# us__2shc.net
KiCad netlist of a schematic drawn in Altium Designer
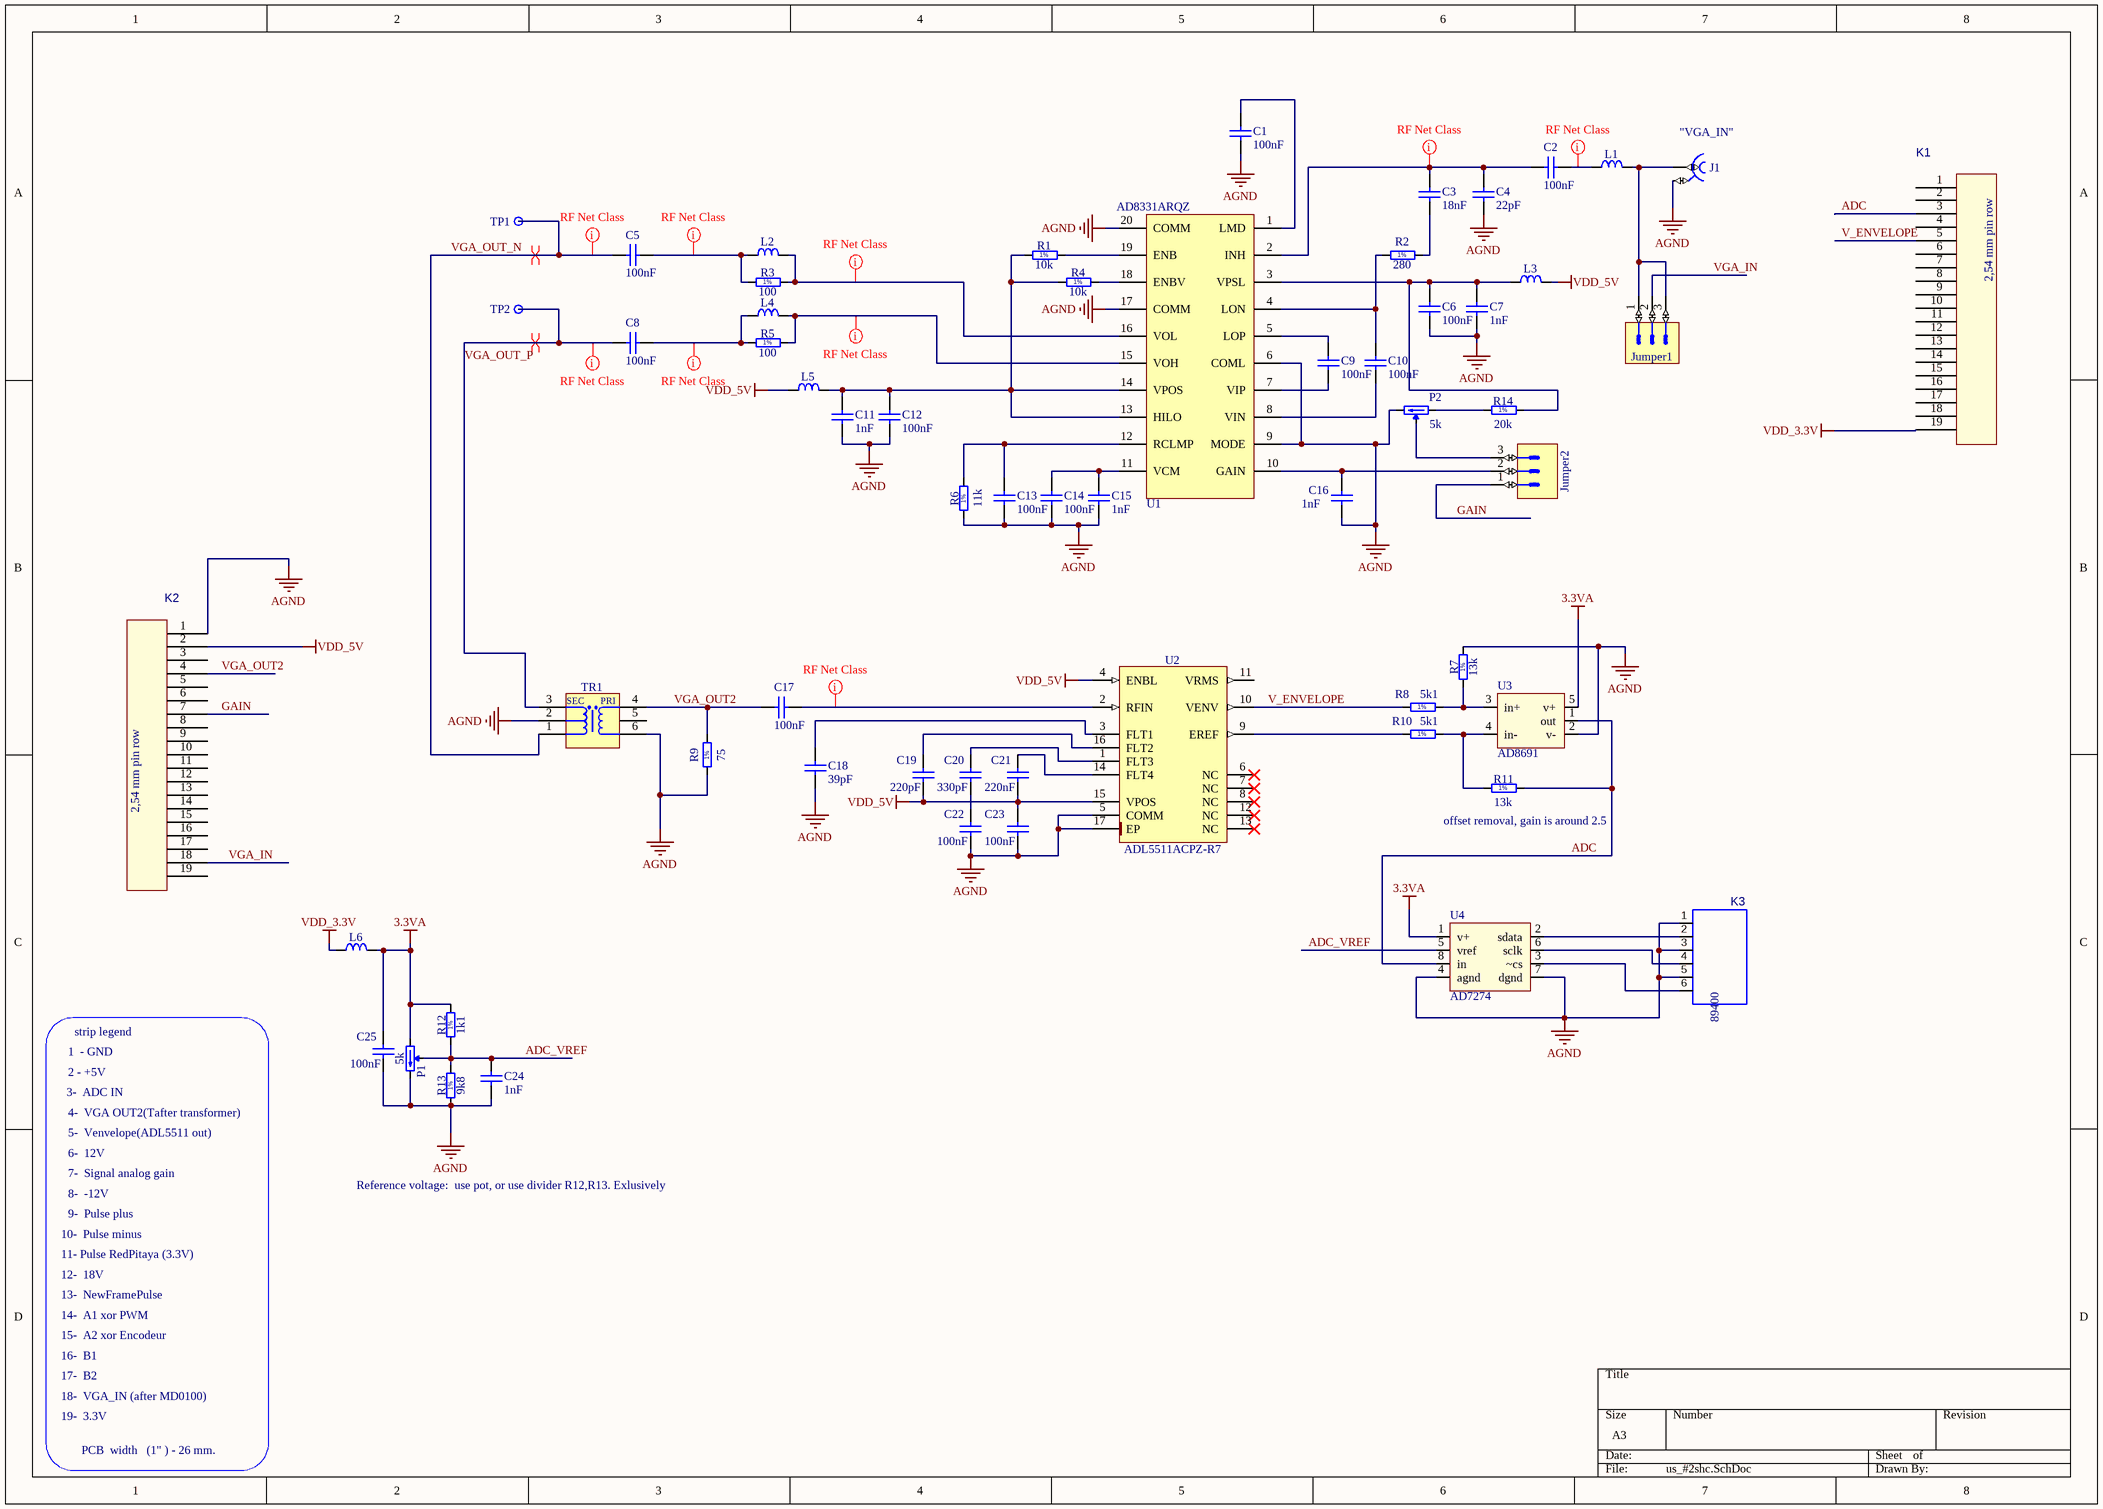
[diagram p0: us_#2shc.SchDoc]

(export (version "E")
  (design (tool "Eeschema 10.0.6"))
  (components
    (comp (ref "C1")
      (value "100nF")
      (footprint "SM0603 _3D_cap")
      (description "Capacitor  0603 inch")
      (fields (field (name "Comment") "cap0603") (field (name "PUBLISHER") "Altium Limited"))
      (libsource (lib "alt_vovan") (part "cap0603"))
    )
    (comp (ref "C2")
      (value "100nF")
      (footprint "SM0603 _3D_cap")
      (description "Capacitor  0603 inch")
      (fields (field (name "Comment") "cap0603") (field (name "PUBLISHER") "Altium Limited"))
      (libsource (lib "alt_vovan") (part "cap0603"))
    )
    (comp (ref "C3")
      (value "18nF")
      (footprint "SM0603 _3D_cap")
      (description "Capacitor  0603 inch")
      (fields (field (name "Comment") "cap0603") (field (name "PUBLISHER") "Altium Limited"))
      (libsource (lib "alt_vovan") (part "cap0603"))
    )
    (comp (ref "C4")
      (value "22pF")
      (footprint "SM0603 _3D_cap")
      (description "Capacitor  0603 inch")
      (fields (field (name "Comment") "cap0603") (field (name "PUBLISHER") "Altium Limited"))
      (libsource (lib "alt_vovan") (part "cap0603"))
    )
    (comp (ref "C5")
      (value "100nF")
      (footprint "SM0603 _3D_cap")
      (description "Capacitor  0603 inch")
      (fields (field (name "Comment") "cap0603") (field (name "PUBLISHER") "Altium Limited"))
      (libsource (lib "alt_vovan") (part "cap0603"))
    )
    (comp (ref "C6")
      (value "100nF")
      (footprint "SM0603 _3D_cap")
      (description "Capacitor  0603 inch")
      (fields (field (name "Comment") "cap0603") (field (name "PUBLISHER") "Altium Limited"))
      (libsource (lib "alt_vovan") (part "cap0603"))
    )
    (comp (ref "C7")
      (value "1nF")
      (footprint "SM0603 _3D_cap")
      (description "Capacitor  0603 inch")
      (fields (field (name "Comment") "cap0603") (field (name "PUBLISHER") "Altium Limited"))
      (libsource (lib "alt_vovan") (part "cap0603"))
    )
    (comp (ref "C8")
      (value "100nF")
      (footprint "SM0603 _3D_cap")
      (description "Capacitor  0603 inch")
      (fields (field (name "Comment") "cap0603") (field (name "PUBLISHER") "Altium Limited"))
      (libsource (lib "alt_vovan") (part "cap0603"))
    )
    (comp (ref "C9")
      (value "100nF")
      (footprint "SM0603 _3D_cap")
      (description "Capacitor  0603 inch")
      (fields (field (name "Comment") "cap0603") (field (name "PUBLISHER") "Altium Limited"))
      (libsource (lib "alt_vovan") (part "cap0603"))
    )
    (comp (ref "C10")
      (value "100nF")
      (footprint "SM0603 _3D_cap")
      (description "Capacitor  0603 inch")
      (fields (field (name "Comment") "cap0603") (field (name "PUBLISHER") "Altium Limited"))
      (libsource (lib "alt_vovan") (part "cap0603"))
    )
    (comp (ref "C11")
      (value "1nF")
      (footprint "SM0603 _3D_cap")
      (description "Capacitor  0603 inch")
      (fields (field (name "Comment") "cap0603") (field (name "PUBLISHER") "Altium Limited"))
      (libsource (lib "alt_vovan") (part "cap0603"))
    )
    (comp (ref "C12")
      (value "100nF")
      (footprint "SM0603 _3D_cap")
      (description "Capacitor  0603 inch")
      (fields (field (name "Comment") "cap0603") (field (name "PUBLISHER") "Altium Limited"))
      (libsource (lib "alt_vovan") (part "cap0603"))
    )
    (comp (ref "C13")
      (value "100nF")
      (footprint "SM0603 _3D_cap")
      (description "Capacitor  0603 inch")
      (fields (field (name "Comment") "cap0603") (field (name "PUBLISHER") "Altium Limited"))
      (libsource (lib "alt_vovan") (part "cap0603"))
    )
    (comp (ref "C14")
      (value "100nF")
      (footprint "SM0603 _3D_cap")
      (description "Capacitor  0603 inch")
      (fields (field (name "Comment") "cap0603") (field (name "PUBLISHER") "Altium Limited"))
      (libsource (lib "alt_vovan") (part "cap0603"))
    )
    (comp (ref "C15")
      (value "1nF")
      (footprint "SM0603 _3D_cap")
      (description "Capacitor  0603 inch")
      (fields (field (name "Comment") "cap0603") (field (name "PUBLISHER") "Altium Limited"))
      (libsource (lib "alt_vovan") (part "cap0603"))
    )
    (comp (ref "C16")
      (value "1nF")
      (footprint "SM0603 _3D_cap")
      (description "Capacitor  0603 inch")
      (fields (field (name "Comment") "cap0603") (field (name "PUBLISHER") "Altium Limited"))
      (libsource (lib "alt_vovan") (part "cap0603"))
    )
    (comp (ref "C17")
      (value "100nF")
      (footprint "SM0603 _3D_cap")
      (description "Capacitor  0603 inch")
      (fields (field (name "Comment") "cap0603") (field (name "PUBLISHER") "Altium Limited"))
      (libsource (lib "alt_vovan") (part "cap0603"))
    )
    (comp (ref "C18")
      (value "39pF")
      (footprint "SM0603 _3D_cap")
      (description "Capacitor  0603 inch")
      (fields (field (name "Comment") "cap0603") (field (name "PUBLISHER") "Altium Limited"))
      (libsource (lib "alt_vovan") (part "cap0603"))
    )
    (comp (ref "C19")
      (value "220pF")
      (footprint "SM0603 _3D_cap")
      (description "Capacitor  0603 inch")
      (fields (field (name "Comment") "cap0603") (field (name "PUBLISHER") "Altium Limited"))
      (libsource (lib "alt_vovan") (part "cap0603"))
    )
    (comp (ref "C20")
      (value "330pF")
      (footprint "SM0603 _3D_cap")
      (description "Capacitor  0603 inch")
      (fields (field (name "Comment") "cap0603") (field (name "PUBLISHER") "Altium Limited"))
      (libsource (lib "alt_vovan") (part "cap0603"))
    )
    (comp (ref "C21")
      (value "220nF")
      (footprint "SM0603 _3D_cap")
      (description "Capacitor  0603 inch")
      (fields (field (name "Comment") "cap0603") (field (name "PUBLISHER") "Altium Limited"))
      (libsource (lib "alt_vovan") (part "cap0603"))
    )
    (comp (ref "C22")
      (value "100nF")
      (footprint "SM0603 _3D_cap")
      (description "Capacitor  0603 inch")
      (fields (field (name "Comment") "cap0603") (field (name "PUBLISHER") "Altium Limited"))
      (libsource (lib "alt_vovan") (part "cap0603"))
    )
    (comp (ref "C23")
      (value "100nF")
      (footprint "SM0603 _3D_cap")
      (description "Capacitor  0603 inch")
      (fields (field (name "Comment") "cap0603") (field (name "PUBLISHER") "Altium Limited"))
      (libsource (lib "alt_vovan") (part "cap0603"))
    )
    (comp (ref "C24")
      (value "1nF")
      (footprint "SM0603 _3D_cap")
      (description "Capacitor  0603 inch")
      (fields (field (name "Comment") "cap0603") (field (name "PUBLISHER") "Altium Limited"))
      (libsource (lib "alt_vovan") (part "cap0603"))
    )
    (comp (ref "C25")
      (value "100nF")
      (footprint "SM0603 _3D_cap")
      (description "Capacitor  0603 inch")
      (fields (field (name "Comment") "cap0603") (field (name "PUBLISHER") "Altium Limited"))
      (libsource (lib "alt_vovan") (part "cap0603"))
    )
    (comp (ref "J1")
      (value "SMA")
      (footprint "AMPHENOL_132357-11")
      (fields
        (field (name "PART NUMBER") "AMPHENOL_132357-11")
        (field (name "MANUFACTURER") "AMPHENOL")
        (field (name "MANUFACTURER PART NUMBER") "132357-11")
        (field (name "AUTHOR") "CERN DEM JLC")
      )
      (libsource (lib "echOpen_ADC_Card") (part "Coax_1Female_1Shield"))
    )
    (comp (ref "Jumper1")
      (value "~")
      (footprint "SULLINS_GRPB031VWVN")
      (description "Connector 3 Male")
      (fields
        (field (name "PART NUMBER") "SULLINS_GRPB031VWVN")
        (field (name "MANUFACTURER") "SULLINS")
        (field (name "AUTHOR") "S. Jafar")
      )
      (libsource (lib "") (part "Connector 3 Male_1"))
    )
    (comp (ref "Jumper2")
      (value "~")
      (footprint "SULLINS_GRPB031VWVN")
      (description "Connector 3 Male")
      (fields
        (field (name "PART NUMBER") "SULLINS_GRPB031VWVN")
        (field (name "MANUFACTURER") "SULLINS")
        (field (name "AUTHOR") "S. Jafar")
      )
      (libsource (lib "Sof-Connectors") (part "Connector 3 Male"))
    )
    (comp (ref "K1")
      (value "PLS_2.54mm-19")
      (footprint "PLS_2.54mm-19")
      (libsource (lib "") (part "PLS_2.54mm-19_1"))
    )
    (comp (ref "K2")
      (value "PLS_2.54mm-19")
      (footprint "PLS_2.54mm-19")
      (libsource (lib "alt_vovan") (part "PLS_2.54mm-19"))
    )
    (comp (ref "K3")
      (value "Molex_89400_061")
      (footprint "Molex_89400-061")
      (description "6 pin vertical 2mm")
      (libsource (lib "alt_vovan") (part "Molex_89400_061"))
    )
    (comp (ref "L1")
      (value "75R@100MHz")
      (footprint "SM_0805_INDUCTANCE _3D")
      (description "chip inductance")
      (fields
        (field (name "PART NUMBER") "IND0805_MURATA_BLM21BB750SN1D")
        (field (name "POWER") "700mA")
        (field (name "AUTHOR") "S. Jafar")
      )
      (libsource (lib "alt_vovan") (part "Ind_Chip"))
    )
    (comp (ref "L2")
      (value "75R@100MHz")
      (footprint "SM_0805_INDUCTANCE _3D")
      (description "chip inductance")
      (fields
        (field (name "PART NUMBER") "IND0805_MURATA_BLM21BB750SN1D")
        (field (name "POWER") "700mA")
        (field (name "AUTHOR") "S. Jafar")
      )
      (libsource (lib "alt_vovan") (part "Ind_Chip"))
    )
    (comp (ref "L3")
      (value "75R@100MHz")
      (footprint "SM_0805_INDUCTANCE _3D")
      (description "chip inductance")
      (fields
        (field (name "PART NUMBER") "IND0805_MURATA_BLM21BB750SN1D")
        (field (name "POWER") "700mA")
        (field (name "AUTHOR") "S. Jafar")
      )
      (libsource (lib "alt_vovan") (part "Ind_Chip"))
    )
    (comp (ref "L4")
      (value "75R@100MHz")
      (footprint "SM_0805_INDUCTANCE _3D")
      (description "chip inductance")
      (fields
        (field (name "PART NUMBER") "IND0805_MURATA_BLM21BB750SN1D")
        (field (name "POWER") "700mA")
        (field (name "AUTHOR") "S. Jafar")
      )
      (libsource (lib "alt_vovan") (part "Ind_Chip"))
    )
    (comp (ref "L5")
      (value "75R@100MHz")
      (footprint "SM_0805_INDUCTANCE _3D")
      (description "chip inductance")
      (fields
        (field (name "PART NUMBER") "IND0805_MURATA_BLM21BB750SN1D")
        (field (name "POWER") "700mA")
        (field (name "AUTHOR") "S. Jafar")
      )
      (libsource (lib "alt_vovan") (part "Ind_Chip"))
    )
    (comp (ref "L6")
      (value "75R@100MHz")
      (footprint "SM_0805_INDUCTANCE _3D")
      (description "chip inductance")
      (fields
        (field (name "PART NUMBER") "IND0805_MURATA_BLM21BB750SN1D")
        (field (name "POWER") "700mA")
        (field (name "AUTHOR") "S. Jafar")
      )
      (libsource (lib "alt_vovan") (part "Ind_Chip"))
    )
    (comp (ref "P1")
      (value "5k")
      (footprint "TRIM_BOURNS_3223W")
      (description "Trimming Potentiometer")
      (fields
        (field (name "PART NUMBER") "TRIM_11T_5K_BOURNS_3223W-1-502E")
        (field (name "POWER") "0.125W")
        (field (name "AUTHOR") "CERN DEM JLC")
      )
      (libsource (lib "echOpen_ADC_Card") (part "Trimming Potentiometer"))
    )
    (comp (ref "P2")
      (value "5k")
      (footprint "TRIM_BOURNS_3223W")
      (description "Trimming Potentiometer")
      (fields
        (field (name "PART NUMBER") "TRIM_11T_5K_BOURNS_3223W-1-502E")
        (field (name "POWER") "0.125W")
        (field (name "AUTHOR") "CERN DEM JLC")
      )
      (libsource (lib "echOpen_ADC_Card") (part "Trimming Potentiometer"))
    )
    (comp (ref "R1")
      (value "10k")
      (footprint "SM0603_3D_res")
      (description "Res_0603_1%_EU")
      (fields
        (field (name "PART NUMBER") "R1206_4K7_1%_0.25W_100PPM")
        (field (name "POWER") "0.25W")
        (field (name "AUTHOR") "CERN DEM JLC")
      )
      (libsource (lib "alt_vovan") (part "Res_0603_1%_EU"))
    )
    (comp (ref "R2")
      (value "280")
      (footprint "SM0603_3D_res")
      (description "Res_0603_1%_EU")
      (fields
        (field (name "PART NUMBER") "R1206_4K7_1%_0.25W_100PPM")
        (field (name "POWER") "0.25W")
        (field (name "AUTHOR") "CERN DEM JLC")
      )
      (libsource (lib "alt_vovan") (part "Res_0603_1%_EU"))
    )
    (comp (ref "R3")
      (value "100")
      (footprint "SM0603_3D_res")
      (description "Res_0603_1%_EU")
      (fields
        (field (name "PART NUMBER") "R1206_4K7_1%_0.25W_100PPM")
        (field (name "POWER") "0.25W")
        (field (name "AUTHOR") "CERN DEM JLC")
      )
      (libsource (lib "alt_vovan") (part "Res_0603_1%_EU"))
    )
    (comp (ref "R4")
      (value "10k")
      (footprint "SM0603_3D_res")
      (description "Res_0603_1%_EU")
      (fields
        (field (name "PART NUMBER") "R1206_4K7_1%_0.25W_100PPM")
        (field (name "POWER") "0.25W")
        (field (name "AUTHOR") "CERN DEM JLC")
      )
      (libsource (lib "alt_vovan") (part "Res_0603_1%_EU"))
    )
    (comp (ref "R5")
      (value "100")
      (footprint "SM0603_3D_res")
      (description "Res_0603_1%_EU")
      (fields
        (field (name "PART NUMBER") "R1206_4K7_1%_0.25W_100PPM")
        (field (name "POWER") "0.25W")
        (field (name "AUTHOR") "CERN DEM JLC")
      )
      (libsource (lib "alt_vovan") (part "Res_0603_1%_EU"))
    )
    (comp (ref "R6")
      (value "11k")
      (footprint "SM0603_3D_res")
      (description "Res_0603_1%_EU")
      (fields
        (field (name "PART NUMBER") "R1206_4K7_1%_0.25W_100PPM")
        (field (name "POWER") "0.25W")
        (field (name "AUTHOR") "CERN DEM JLC")
      )
      (libsource (lib "alt_vovan") (part "Res_0603_1%_EU"))
    )
    (comp (ref "R7")
      (value "13k")
      (footprint "SM0603_3D_res")
      (description "Res_0603_1%_EU")
      (fields
        (field (name "PART NUMBER") "R1206_4K7_1%_0.25W_100PPM")
        (field (name "POWER") "0.25W")
        (field (name "AUTHOR") "CERN DEM JLC")
      )
      (libsource (lib "alt_vovan") (part "Res_0603_1%_EU"))
    )
    (comp (ref "R8")
      (value "5k1")
      (footprint "SM0603_3D_res")
      (description "Res_0603_1%_EU")
      (fields
        (field (name "PART NUMBER") "R1206_4K7_1%_0.25W_100PPM")
        (field (name "POWER") "0.25W")
        (field (name "AUTHOR") "CERN DEM JLC")
      )
      (libsource (lib "alt_vovan") (part "Res_0603_1%_EU"))
    )
    (comp (ref "R9")
      (value "75")
      (footprint "SM0603_3D_res")
      (description "Res_0603_1%_EU")
      (fields
        (field (name "PART NUMBER") "R1206_4K7_1%_0.25W_100PPM")
        (field (name "POWER") "0.25W")
        (field (name "AUTHOR") "CERN DEM JLC")
      )
      (libsource (lib "alt_vovan") (part "Res_0603_1%_EU"))
    )
    (comp (ref "R10")
      (value "5k1")
      (footprint "SM0603_3D_res")
      (description "Res_0603_1%_EU")
      (fields
        (field (name "PART NUMBER") "R1206_4K7_1%_0.25W_100PPM")
        (field (name "POWER") "0.25W")
        (field (name "AUTHOR") "CERN DEM JLC")
      )
      (libsource (lib "alt_vovan") (part "Res_0603_1%_EU"))
    )
    (comp (ref "R11")
      (value "13k")
      (footprint "SM0603_3D_res")
      (description "Res_0603_1%_EU")
      (fields
        (field (name "PART NUMBER") "R1206_4K7_1%_0.25W_100PPM")
        (field (name "POWER") "0.25W")
        (field (name "AUTHOR") "CERN DEM JLC")
      )
      (libsource (lib "alt_vovan") (part "Res_0603_1%_EU"))
    )
    (comp (ref "R12")
      (value "1k1")
      (footprint "SM0603_3D_res")
      (description "Res_0603_1%_EU")
      (fields
        (field (name "PART NUMBER") "R1206_4K7_1%_0.25W_100PPM")
        (field (name "POWER") "0.25W")
        (field (name "AUTHOR") "CERN DEM JLC")
      )
      (libsource (lib "alt_vovan") (part "Res_0603_1%_EU"))
    )
    (comp (ref "R13")
      (value "9k8")
      (footprint "SM0603_3D_res")
      (description "Res_0603_1%_EU")
      (fields
        (field (name "PART NUMBER") "R1206_4K7_1%_0.25W_100PPM")
        (field (name "POWER") "0.25W")
        (field (name "AUTHOR") "CERN DEM JLC")
      )
      (libsource (lib "alt_vovan") (part "Res_0603_1%_EU"))
    )
    (comp (ref "R14")
      (value "20k")
      (footprint "SM0603_3D_res")
      (description "Res_0603_1%_EU")
      (fields
        (field (name "PART NUMBER") "R1206_4K7_1%_0.25W_100PPM")
        (field (name "POWER") "0.25W")
        (field (name "AUTHOR") "CERN DEM JLC")
      )
      (libsource (lib "alt_vovan") (part "Res_0603_1%_EU"))
    )
    (comp (ref "TP1")
      (value "Test Point")
      (footprint "NICOMATIC_C12000B")
      (fields
        (field (name "PART NUMBER") "NICOMATIC_C12000B")
        (field (name "MANUFACTURER") "NICOMATIC")
        (field (name "MANUFACTURER PART NUMBER") "C12000B")
        (field (name "AUTHOR") "CERN DEM JLC")
      )
      (libsource (lib "Sof-Connectors") (part "Test Point"))
    )
    (comp (ref "TP2")
      (value "Test Point")
      (footprint "NICOMATIC_C12000B")
      (fields
        (field (name "PART NUMBER") "NICOMATIC_C12000B")
        (field (name "MANUFACTURER") "NICOMATIC")
        (field (name "MANUFACTURER PART NUMBER") "C12000B")
        (field (name "AUTHOR") "CERN DEM JLC")
      )
      (libsource (lib "Sof-Connectors") (part "Test Point"))
    )
    (comp (ref "TR1")
      (value "1:1")
      (footprint "XFMR_MINI-CIRCUITS_KK81")
      (description "50 Ohm 0.015 To 300MHz RF Transformers")
      (fields
        (field (name "PART NUMBER") "XFMR_MINI-CIRCUITS_T1-6T-KK81")
        (field (name "MANUFACTURER") "MINI-CIRCUITS")
        (field (name "AUTHOR") "S. Jafar")
      )
      (libsource (lib "Sof-Inductors & Transformers") (part "XFMR_MINI-CIRCUITS_T1-6T-KK81"))
    )
    (comp (ref "U1")
      (value "AD8331ARQZ")
      (footprint "SOP64P600X175-20N")
      (fields (field (name "MANUFACTURER") "Analog Devices") (field (name "AUTHOR") "S. Jafar"))
      (libsource (lib "Sof-ICs And Semiconductors") (part "AD8331"))
    )
    (comp (ref "U2")
      (value "ADL5511ACPZ-R7")
      (footprint "QFN50P300X300X80-17N-S175")
      (description "DC to 6 GHz Envelope and TruPwr RMS Detector")
      (fields (field (name "MANUFACTURER") "ANALOG DEVICES") (field (name "AUTHOR") "CERN DEM JLC"))
      (libsource (lib "Sof-ICs And Semiconductors") (part "ADL5511"))
    )
    (comp (ref "U3")
      (value "AD8691")
      (footprint "TSOT-5(RT-5)")
      (libsource (lib "alt_vovan") (part "OpAmp_TSOT5"))
    )
    (comp (ref "U4")
      (value "AD7274")
      (footprint "RM-8")
      (description "adc serial")
      (libsource (lib "alt_vovan") (part "AD7274"))
    )
  )
  (nets
    (net (code "1") (name "/ADC") (class "Default")
      (node (ref "K1") (pin "3") (pinfunction "3_3") (pintype "passive"))
      (node (ref "R11") (pin "2") (pinfunction "2_2") (pintype "passive"))
      (node (ref "U3") (pin "1") (pinfunction "out_1") (pintype "passive"))
      (node (ref "U4") (pin "8") (pinfunction "in_8") (pintype "passive"))
    )
    (net (code "2") (name "/ADC_VREF") (class "Default")
      (node (ref "C24") (pin "2") (pinfunction "2_2") (pintype "passive"))
      (node (ref "P1") (pin "2") (pinfunction "W_2") (pintype "passive"))
      (node (ref "R12") (pin "1") (pinfunction "1_1") (pintype "passive"))
      (node (ref "R13") (pin "2") (pinfunction "2_2") (pintype "passive"))
      (node (ref "U4") (pin "5") (pinfunction "vref_5") (pintype "passive"))
    )
    (net (code "3") (name "/GAIN") (class "Default")
      (node (ref "Jumper2") (pin "1") (pinfunction "1_1") (pintype "bidirectional"))
      (node (ref "K2") (pin "7") (pinfunction "7_7") (pintype "passive"))
    )
    (net (code "4") (name "/VGA_IN") (class "Default")
      (node (ref "Jumper1") (pin "2") (pinfunction "2_2") (pintype "bidirectional"))
      (node (ref "K2") (pin "18") (pinfunction "18_18") (pintype "passive"))
    )
    (net (code "5") (name "/VGA_OUT2") (class "Default")
      (node (ref "C17") (pin "1") (pinfunction "1_1") (pintype "passive"))
      (node (ref "K2") (pin "4") (pinfunction "4_4") (pintype "passive"))
      (node (ref "R9") (pin "2") (pinfunction "2_2") (pintype "passive"))
      (node (ref "TR1") (pin "4") (pinfunction "SDOT_4") (pintype "passive"))
    )
    (net (code "6") (name "/VGA_OUT_N") (class "Default")
      (node (ref "C5") (pin "1") (pinfunction "1_1") (pintype "passive"))
      (node (ref "TP1") (pin "1") (pinfunction "1_1") (pintype "bidirectional"))
      (node (ref "TR1") (pin "1") (pinfunction "P_1") (pintype "passive"))
    )
    (net (code "7") (name "/VGA_OUT_P") (class "Default")
      (node (ref "C8") (pin "2") (pinfunction "2_2") (pintype "passive"))
      (node (ref "TP2") (pin "1") (pinfunction "1_1") (pintype "bidirectional"))
      (node (ref "TR1") (pin "3") (pinfunction "PDOT_3") (pintype "passive"))
    )
    (net (code "8") (name "/V_ENVELOPE") (class "Default")
      (node (ref "K1") (pin "5") (pinfunction "5_5") (pintype "passive"))
      (node (ref "R8") (pin "1") (pinfunction "1_1") (pintype "passive"))
      (node (ref "U2") (pin "10") (pinfunction "VENV_10") (pintype "output"))
    )
    (net (code "9") (name "3.3VA") (class "Default")
      (node (ref "C25") (pin "2") (pinfunction "2_2") (pintype "passive"))
      (node (ref "L6") (pin "2") (pinfunction "2_2") (pintype "passive"))
      (node (ref "P1") (pin "1") (pinfunction "CCW_1") (pintype "passive"))
      (node (ref "R12") (pin "2") (pinfunction "2_2") (pintype "passive"))
      (node (ref "U3") (pin "5") (pinfunction "v+_5") (pintype "passive"))
      (node (ref "U4") (pin "1") (pinfunction "v+_1") (pintype "passive"))
    )
    (net (code "10") (name "AGND") (class "Default")
      (node (ref "C1") (pin "1") (pinfunction "1_1") (pintype "passive"))
      (node (ref "C11") (pin "1") (pinfunction "1_1") (pintype "passive"))
      (node (ref "C12") (pin "1") (pinfunction "1_1") (pintype "passive"))
      (node (ref "C13") (pin "1") (pinfunction "1_1") (pintype "passive"))
      (node (ref "C14") (pin "1") (pinfunction "1_1") (pintype "passive"))
      (node (ref "C15") (pin "1") (pinfunction "1_1") (pintype "passive"))
      (node (ref "C16") (pin "1") (pinfunction "1_1") (pintype "passive"))
      (node (ref "C18") (pin "1") (pinfunction "1_1") (pintype "passive"))
      (node (ref "C22") (pin "1") (pinfunction "1_1") (pintype "passive"))
      (node (ref "C23") (pin "1") (pinfunction "1_1") (pintype "passive"))
      (node (ref "C24") (pin "1") (pinfunction "1_1") (pintype "passive"))
      (node (ref "C25") (pin "1") (pinfunction "1_1") (pintype "passive"))
      (node (ref "C4") (pin "1") (pinfunction "1_1") (pintype "passive"))
      (node (ref "C6") (pin "1") (pinfunction "1_1") (pintype "passive"))
      (node (ref "C7") (pin "1") (pinfunction "1_1") (pintype "passive"))
      (node (ref "J1") (pin "2") (pinfunction "2_2") (pintype "bidirectional"))
      (node (ref "K2") (pin "1") (pinfunction "1_1") (pintype "passive"))
      (node (ref "K3") (pin "1") (pinfunction "1_1") (pintype "passive"))
      (node (ref "K3") (pin "3") (pinfunction "3_3") (pintype "passive"))
      (node (ref "K3") (pin "5") (pinfunction "5_5") (pintype "passive"))
      (node (ref "P1") (pin "3") (pinfunction "CW_3") (pintype "passive"))
      (node (ref "P2") (pin "3") (pinfunction "CW_3") (pintype "passive"))
      (node (ref "R13") (pin "1") (pinfunction "1_1") (pintype "passive"))
      (node (ref "R6") (pin "1") (pinfunction "1_1") (pintype "passive"))
      (node (ref "R7") (pin "2") (pinfunction "2_2") (pintype "passive"))
      (node (ref "R9") (pin "1") (pinfunction "1_1") (pintype "passive"))
      (node (ref "TR1") (pin "2") (pinfunction "NC_2") (pintype "passive"))
      (node (ref "TR1") (pin "6") (pinfunction "S_6") (pintype "passive"))
      (node (ref "U1") (pin "17") (pinfunction "COMM_17") (pintype "passive"))
      (node (ref "U1") (pin "20") (pinfunction "COMM_20") (pintype "passive"))
      (node (ref "U1") (pin "6") (pinfunction "COML_6") (pintype "passive"))
      (node (ref "U1") (pin "9") (pinfunction "MODE_9") (pintype "passive"))
      (node (ref "U2") (pin "17") (pinfunction "EP_17") (pintype "power_in"))
      (node (ref "U2") (pin "5") (pinfunction "COMM_5") (pintype "power_in"))
      (node (ref "U3") (pin "2") (pinfunction "v-_2") (pintype "passive"))
      (node (ref "U4") (pin "4") (pinfunction "agnd_4") (pintype "passive"))
      (node (ref "U4") (pin "7") (pinfunction "dgnd_7") (pintype "passive"))
    )
    (net (code "11") (name "Net-(C2-Pad2)") (class "Default")
      (node (ref "C2") (pin "2") (pinfunction "2_2") (pintype "passive"))
      (node (ref "L1") (pin "1") (pinfunction "1_1") (pintype "passive"))
    )
    (net (code "12") (name "Net-(C3-Pad1)") (class "Default")
      (node (ref "C3") (pin "1") (pinfunction "1_1") (pintype "passive"))
      (node (ref "R2") (pin "2") (pinfunction "2_2") (pintype "passive"))
    )
    (net (code "13") (name "Net-(C5-Pad2)") (class "Default")
      (node (ref "C5") (pin "2") (pinfunction "2_2") (pintype "passive"))
      (node (ref "L2") (pin "1") (pinfunction "1_1") (pintype "passive"))
      (node (ref "R3") (pin "1") (pinfunction "1_1") (pintype "passive"))
    )
    (net (code "14") (name "Net-(C8-Pad1)") (class "Default")
      (node (ref "C8") (pin "1") (pinfunction "1_1") (pintype "passive"))
      (node (ref "L4") (pin "1") (pinfunction "1_1") (pintype "passive"))
      (node (ref "R5") (pin "1") (pinfunction "1_1") (pintype "passive"))
    )
    (net (code "15") (name "Net-(C20-Pad1)") (class "Default")
      (node (ref "C20") (pin "1") (pinfunction "1_1") (pintype "passive"))
      (node (ref "C22") (pin "2") (pinfunction "2_2") (pintype "passive"))
    )
    (net (code "16") (name "Net-(J1-Pad1)") (class "Default")
      (node (ref "J1") (pin "1") (pinfunction "1_1") (pintype "bidirectional"))
      (node (ref "Jumper1") (pin "1") (pinfunction "1_1") (pintype "bidirectional"))
      (node (ref "Jumper1") (pin "3") (pinfunction "3_3") (pintype "bidirectional"))
      (node (ref "L1") (pin "2") (pinfunction "2_2") (pintype "passive"))
    )
    (net (code "17") (name "Net-(P2-CCW)") (class "Default")
      (node (ref "P2") (pin "1") (pinfunction "CCW_1") (pintype "passive"))
      (node (ref "R14") (pin "1") (pinfunction "1_1") (pintype "passive"))
    )
    (net (code "18") (name "Net-(P2-W)") (class "Default")
      (node (ref "Jumper2") (pin "3") (pinfunction "3_3") (pintype "bidirectional"))
      (node (ref "P2") (pin "2") (pinfunction "W_2") (pintype "passive"))
    )
    (net (code "19") (name "Net-(U1-ENB)") (class "Default")
      (node (ref "R1") (pin "2") (pinfunction "2_2") (pintype "passive"))
      (node (ref "U1") (pin "19") (pinfunction "ENB_19") (pintype "passive"))
    )
    (net (code "20") (name "Net-(U1-ENBV)") (class "Default")
      (node (ref "R4") (pin "2") (pinfunction "2_2") (pintype "passive"))
      (node (ref "U1") (pin "18") (pinfunction "ENBV_18") (pintype "passive"))
    )
    (net (code "21") (name "Net-(U1-GAIN)") (class "Default")
      (node (ref "C16") (pin "2") (pinfunction "2_2") (pintype "passive"))
      (node (ref "Jumper2") (pin "2") (pinfunction "2_2") (pintype "bidirectional"))
      (node (ref "U1") (pin "10") (pinfunction "GAIN_10") (pintype "passive"))
    )
    (net (code "22") (name "Net-(U1-HILO)") (class "Default")
      (node (ref "C11") (pin "2") (pinfunction "2_2") (pintype "passive"))
      (node (ref "C12") (pin "2") (pinfunction "2_2") (pintype "passive"))
      (node (ref "L5") (pin "2") (pinfunction "2_2") (pintype "passive"))
      (node (ref "R1") (pin "1") (pinfunction "1_1") (pintype "passive"))
      (node (ref "R4") (pin "1") (pinfunction "1_1") (pintype "passive"))
      (node (ref "U1") (pin "13") (pinfunction "HILO_13") (pintype "passive"))
      (node (ref "U1") (pin "14") (pinfunction "VPOS_14") (pintype "passive"))
    )
    (net (code "23") (name "Net-(U1-INH)") (class "Default")
      (node (ref "C2") (pin "1") (pinfunction "1_1") (pintype "passive"))
      (node (ref "C3") (pin "2") (pinfunction "2_2") (pintype "passive"))
      (node (ref "C4") (pin "2") (pinfunction "2_2") (pintype "passive"))
      (node (ref "U1") (pin "2") (pinfunction "INH_2") (pintype "passive"))
    )
    (net (code "24") (name "Net-(U1-LMD)") (class "Default")
      (node (ref "C1") (pin "2") (pinfunction "2_2") (pintype "passive"))
      (node (ref "U1") (pin "1") (pinfunction "LMD_1") (pintype "passive"))
    )
    (net (code "25") (name "Net-(U1-LON)") (class "Default")
      (node (ref "C10") (pin "2") (pinfunction "2_2") (pintype "passive"))
      (node (ref "R2") (pin "1") (pinfunction "1_1") (pintype "passive"))
      (node (ref "U1") (pin "4") (pinfunction "LON_4") (pintype "passive"))
    )
    (net (code "26") (name "Net-(U1-LOP)") (class "Default")
      (node (ref "C9") (pin "2") (pinfunction "2_2") (pintype "passive"))
      (node (ref "U1") (pin "5") (pinfunction "LOP_5") (pintype "passive"))
    )
    (net (code "27") (name "Net-(U1-RCLMP)") (class "Default")
      (node (ref "C13") (pin "2") (pinfunction "2_2") (pintype "passive"))
      (node (ref "R6") (pin "2") (pinfunction "2_2") (pintype "passive"))
      (node (ref "U1") (pin "12") (pinfunction "RCLMP_12") (pintype "passive"))
    )
    (net (code "28") (name "Net-(U1-VCM)") (class "Default")
      (node (ref "C14") (pin "2") (pinfunction "2_2") (pintype "passive"))
      (node (ref "C15") (pin "2") (pinfunction "2_2") (pintype "passive"))
      (node (ref "U1") (pin "11") (pinfunction "VCM_11") (pintype "passive"))
    )
    (net (code "29") (name "Net-(U1-VIN)") (class "Default")
      (node (ref "C10") (pin "1") (pinfunction "1_1") (pintype "passive"))
      (node (ref "U1") (pin "8") (pinfunction "VIN_8") (pintype "passive"))
    )
    (net (code "30") (name "Net-(U1-VIP)") (class "Default")
      (node (ref "C9") (pin "1") (pinfunction "1_1") (pintype "passive"))
      (node (ref "U1") (pin "7") (pinfunction "VIP_7") (pintype "passive"))
    )
    (net (code "31") (name "Net-(U1-VOH)") (class "Default")
      (node (ref "L4") (pin "2") (pinfunction "2_2") (pintype "passive"))
      (node (ref "R5") (pin "2") (pinfunction "2_2") (pintype "passive"))
      (node (ref "U1") (pin "15") (pinfunction "VOH_15") (pintype "passive"))
    )
    (net (code "32") (name "Net-(U1-VOL)") (class "Default")
      (node (ref "L2") (pin "2") (pinfunction "2_2") (pintype "passive"))
      (node (ref "R3") (pin "2") (pinfunction "2_2") (pintype "passive"))
      (node (ref "U1") (pin "16") (pinfunction "VOL_16") (pintype "passive"))
    )
    (net (code "33") (name "Net-(U1-VPSL)") (class "Default")
      (node (ref "C6") (pin "2") (pinfunction "2_2") (pintype "passive"))
      (node (ref "C7") (pin "2") (pinfunction "2_2") (pintype "passive"))
      (node (ref "L3") (pin "1") (pinfunction "1_1") (pintype "passive"))
      (node (ref "R14") (pin "2") (pinfunction "2_2") (pintype "passive"))
      (node (ref "U1") (pin "3") (pinfunction "VPSL_3") (pintype "passive"))
    )
    (net (code "34") (name "Net-(U2-EREF)") (class "Default")
      (node (ref "R10") (pin "1") (pinfunction "1_1") (pintype "passive"))
      (node (ref "U2") (pin "9") (pinfunction "EREF_9") (pintype "output"))
    )
    (net (code "35") (name "Net-(U2-FLT1)") (class "Default")
      (node (ref "C18") (pin "2") (pinfunction "2_2") (pintype "passive"))
      (node (ref "U2") (pin "3") (pinfunction "FLT1_3") (pintype "passive"))
    )
    (net (code "36") (name "Net-(U2-FLT2)") (class "Default")
      (node (ref "C19") (pin "2") (pinfunction "2_2") (pintype "passive"))
      (node (ref "U2") (pin "16") (pinfunction "FLT2_16") (pintype "passive"))
    )
    (net (code "37") (name "Net-(U2-FLT3)") (class "Default")
      (node (ref "C20") (pin "2") (pinfunction "2_2") (pintype "passive"))
      (node (ref "U2") (pin "1") (pinfunction "FLT3_1") (pintype "passive"))
    )
    (net (code "38") (name "Net-(U2-FLT4)") (class "Default")
      (node (ref "C21") (pin "2") (pinfunction "2_2") (pintype "passive"))
      (node (ref "U2") (pin "14") (pinfunction "FLT4_14") (pintype "passive"))
    )
    (net (code "39") (name "Net-(U2-RFIN)") (class "Default")
      (node (ref "C17") (pin "2") (pinfunction "2_2") (pintype "passive"))
      (node (ref "U2") (pin "2") (pinfunction "RFIN_2") (pintype "input"))
    )
    (net (code "40") (name "Net-(U3-in+)") (class "Default")
      (node (ref "R7") (pin "1") (pinfunction "1_1") (pintype "passive"))
      (node (ref "R8") (pin "2") (pinfunction "2_2") (pintype "passive"))
      (node (ref "U3") (pin "3") (pinfunction "in+_3") (pintype "passive"))
    )
    (net (code "41") (name "Net-(U3-in-)") (class "Default")
      (node (ref "R10") (pin "2") (pinfunction "2_2") (pintype "passive"))
      (node (ref "R11") (pin "1") (pinfunction "1_1") (pintype "passive"))
      (node (ref "U3") (pin "4") (pinfunction "in-_4") (pintype "passive"))
    )
    (net (code "42") (name "Net-(U4-sclk)") (class "Default")
      (node (ref "K3") (pin "4") (pinfunction "4_4") (pintype "passive"))
      (node (ref "U4") (pin "6") (pinfunction "sclk_6") (pintype "passive"))
    )
    (net (code "43") (name "Net-(U4-sdata)") (class "Default")
      (node (ref "K3") (pin "2") (pinfunction "2_2") (pintype "passive"))
      (node (ref "U4") (pin "2") (pinfunction "sdata_2") (pintype "passive"))
    )
    (net (code "44") (name "Net-(U4-~cs)") (class "Default")
      (node (ref "K3") (pin "6") (pinfunction "6_6") (pintype "passive"))
      (node (ref "U4") (pin "3") (pinfunction "~cs_3") (pintype "passive"))
    )
    (net (code "45") (name "VDD_3.3V") (class "Default")
      (node (ref "K1") (pin "19") (pinfunction "19_19") (pintype "passive"))
      (node (ref "L6") (pin "1") (pinfunction "1_1") (pintype "passive"))
    )
    (net (code "46") (name "VDD_5V") (class "Default")
      (node (ref "C19") (pin "1") (pinfunction "1_1") (pintype "passive"))
      (node (ref "C21") (pin "1") (pinfunction "1_1") (pintype "passive"))
      (node (ref "C23") (pin "2") (pinfunction "2_2") (pintype "passive"))
      (node (ref "K2") (pin "2") (pinfunction "2_2") (pintype "passive"))
      (node (ref "L3") (pin "2") (pinfunction "2_2") (pintype "passive"))
      (node (ref "L5") (pin "1") (pinfunction "1_1") (pintype "passive"))
      (node (ref "U2") (pin "15") (pinfunction "VPOS_15") (pintype "power_in"))
      (node (ref "U2") (pin "4") (pinfunction "ENBL_4") (pintype "input"))
    )
    (net (code "47") (name "unconnected-(K1-Pad1)") (class "Default")
      (node (ref "K1") (pin "1") (pinfunction "1_1") (pintype "passive"))
    )
    (net (code "48") (name "unconnected-(K1-Pad2)") (class "Default")
      (node (ref "K1") (pin "2") (pinfunction "2_2") (pintype "passive"))
    )
    (net (code "49") (name "unconnected-(K1-Pad4)") (class "Default")
      (node (ref "K1") (pin "4") (pinfunction "4_4") (pintype "passive"))
    )
    (net (code "50") (name "unconnected-(K1-Pad6)") (class "Default")
      (node (ref "K1") (pin "6") (pinfunction "6_6") (pintype "passive"))
    )
    (net (code "51") (name "unconnected-(K1-Pad7)") (class "Default")
      (node (ref "K1") (pin "7") (pinfunction "7_7") (pintype "passive"))
    )
    (net (code "52") (name "unconnected-(K1-Pad8)") (class "Default")
      (node (ref "K1") (pin "8") (pinfunction "8_8") (pintype "passive"))
    )
    (net (code "53") (name "unconnected-(K1-Pad9)") (class "Default")
      (node (ref "K1") (pin "9") (pinfunction "9_9") (pintype "passive"))
    )
    (net (code "54") (name "unconnected-(K1-Pad10)") (class "Default")
      (node (ref "K1") (pin "10") (pinfunction "10_10") (pintype "passive"))
    )
    (net (code "55") (name "unconnected-(K1-Pad11)") (class "Default")
      (node (ref "K1") (pin "11") (pinfunction "11_11") (pintype "passive"))
    )
    (net (code "56") (name "unconnected-(K1-Pad12)") (class "Default")
      (node (ref "K1") (pin "12") (pinfunction "12_12") (pintype "passive"))
    )
    (net (code "57") (name "unconnected-(K1-Pad13)") (class "Default")
      (node (ref "K1") (pin "13") (pinfunction "13_13") (pintype "passive"))
    )
    (net (code "58") (name "unconnected-(K1-Pad14)") (class "Default")
      (node (ref "K1") (pin "14") (pinfunction "14_14") (pintype "passive"))
    )
    (net (code "59") (name "unconnected-(K1-Pad15)") (class "Default")
      (node (ref "K1") (pin "15") (pinfunction "15_15") (pintype "passive"))
    )
    (net (code "60") (name "unconnected-(K1-Pad16)") (class "Default")
      (node (ref "K1") (pin "16") (pinfunction "16_16") (pintype "passive"))
    )
    (net (code "61") (name "unconnected-(K1-Pad17)") (class "Default")
      (node (ref "K1") (pin "17") (pinfunction "17_17") (pintype "passive"))
    )
    (net (code "62") (name "unconnected-(K1-Pad18)") (class "Default")
      (node (ref "K1") (pin "18") (pinfunction "18_18") (pintype "passive"))
    )
    (net (code "63") (name "unconnected-(K2-Pad3)") (class "Default")
      (node (ref "K2") (pin "3") (pinfunction "3_3") (pintype "passive"))
    )
    (net (code "64") (name "unconnected-(K2-Pad5)") (class "Default")
      (node (ref "K2") (pin "5") (pinfunction "5_5") (pintype "passive"))
    )
    (net (code "65") (name "unconnected-(K2-Pad6)") (class "Default")
      (node (ref "K2") (pin "6") (pinfunction "6_6") (pintype "passive"))
    )
    (net (code "66") (name "unconnected-(K2-Pad8)") (class "Default")
      (node (ref "K2") (pin "8") (pinfunction "8_8") (pintype "passive"))
    )
    (net (code "67") (name "unconnected-(K2-Pad9)") (class "Default")
      (node (ref "K2") (pin "9") (pinfunction "9_9") (pintype "passive"))
    )
    (net (code "68") (name "unconnected-(K2-Pad10)") (class "Default")
      (node (ref "K2") (pin "10") (pinfunction "10_10") (pintype "passive"))
    )
    (net (code "69") (name "unconnected-(K2-Pad11)") (class "Default")
      (node (ref "K2") (pin "11") (pinfunction "11_11") (pintype "passive"))
    )
    (net (code "70") (name "unconnected-(K2-Pad12)") (class "Default")
      (node (ref "K2") (pin "12") (pinfunction "12_12") (pintype "passive"))
    )
    (net (code "71") (name "unconnected-(K2-Pad13)") (class "Default")
      (node (ref "K2") (pin "13") (pinfunction "13_13") (pintype "passive"))
    )
    (net (code "72") (name "unconnected-(K2-Pad14)") (class "Default")
      (node (ref "K2") (pin "14") (pinfunction "14_14") (pintype "passive"))
    )
    (net (code "73") (name "unconnected-(K2-Pad15)") (class "Default")
      (node (ref "K2") (pin "15") (pinfunction "15_15") (pintype "passive"))
    )
    (net (code "74") (name "unconnected-(K2-Pad16)") (class "Default")
      (node (ref "K2") (pin "16") (pinfunction "16_16") (pintype "passive"))
    )
    (net (code "75") (name "unconnected-(K2-Pad17)") (class "Default")
      (node (ref "K2") (pin "17") (pinfunction "17_17") (pintype "passive"))
    )
    (net (code "76") (name "unconnected-(K2-Pad19)") (class "Default")
      (node (ref "K2") (pin "19") (pinfunction "19_19") (pintype "passive"))
    )
    (net (code "77") (name "unconnected-(TR1-NC-Pad5)") (class "Default")
      (node (ref "TR1") (pin "5") (pinfunction "NC_5") (pintype "passive"))
    )
    (net (code "78") (name "unconnected-(U2-NC-Pad6)") (class "Default")
      (node (ref "U2") (pin "6") (pinfunction "NC_6") (pintype "passive+no_connect"))
    )
    (net (code "79") (name "unconnected-(U2-NC-Pad7)") (class "Default")
      (node (ref "U2") (pin "7") (pinfunction "NC_7") (pintype "passive+no_connect"))
    )
    (net (code "80") (name "unconnected-(U2-NC-Pad8)") (class "Default")
      (node (ref "U2") (pin "8") (pinfunction "NC_8") (pintype "passive+no_connect"))
    )
    (net (code "81") (name "unconnected-(U2-NC-Pad12)") (class "Default")
      (node (ref "U2") (pin "12") (pinfunction "NC_12") (pintype "passive+no_connect"))
    )
    (net (code "82") (name "unconnected-(U2-NC-Pad13)") (class "Default")
      (node (ref "U2") (pin "13") (pinfunction "NC_13") (pintype "passive+no_connect"))
    )
    (net (code "83") (name "unconnected-(U2-VRMS-Pad11)") (class "Default")
      (node (ref "U2") (pin "11") (pinfunction "VRMS_11") (pintype "output"))
    )
  )
)
